# Shut_Down_Signal_Control.net
KiCad netlist of a schematic drawn in Altium Designer
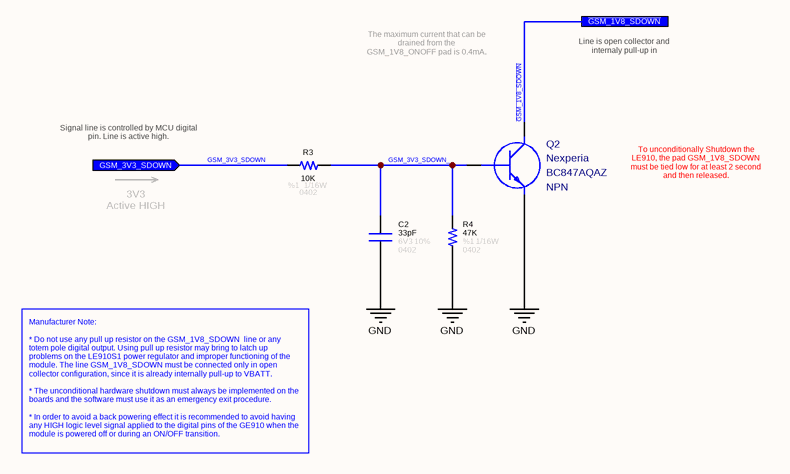
[diagram p0: Shut Down Signal Control.SchDoc]

(export (version "E")
  (design (tool "Eeschema 10.0.6"))
  (components
    (comp (ref "C2")
      (value "33pF")
      (footprint "CAPACITOR_0402")
      (description "Capacitor - 33pF [0402] (Ceramic)")
      (fields
        (field (name "MANUFACTURER PART NUMBER") "C0402C330J9RACAUTO")
        (field (name "TOLERANCE") "10%")
        (field (name "CASE") "0402")
        (field (name "VOLTAGE") "6V3")
      )
      (libsource (lib "P101DA_Library") (part "Capacitor - 33pF [0402-6V3]"))
    )
    (comp (ref "Q2")
      (value "BC847AQAZ")
      (footprint "SOT1215")
      (description "Bipolar NPN Transistors")
      (fields
        (field (name "MANUFACTURER NAME") "Nexperia")
        (field (name "MANUFACTURER PART NUMBER") "BC847AQAZ")
        (field (name "POLARITY") "NPN")
      )
      (libsource (lib "P101DA_Library") (part "Transistor - BC847"))
    )
    (comp (ref "R3")
      (value "10K")
      (footprint "RESISTOR_0402")
      (description "Thick Film Resistors - SMD 1/16 W 10 KOhm 1%")
      (fields
        (field (name "MANUFACTURER PART NUMBER") "CRCW040210K0FKED")
        (field (name "TOLERANCE") "%1")
        (field (name "CASE") "0402")
        (field (name "POWER") "1/16W")
        (field (name "Comment") "10K - 0402 - %1 - 1/16W")
      )
      (libsource (lib "P101DA_Library") (part "Resistor - 10K [0402]"))
    )
    (comp (ref "R4")
      (value "47K")
      (footprint "RESISTOR_0402")
      (description "Thick Film Resistors - SMD 1/16 W 47 KOhm 1%")
      (fields
        (field (name "MANUFACTURER PART NUMBER") "CRCW040247K0FKED")
        (field (name "TOLERANCE") "%1")
        (field (name "CASE") "0402")
        (field (name "POWER") "1/16W")
        (field (name "Comment") "47K - 0402 - %1 - 1/16W")
      )
      (libsource (lib "P101DA_Library") (part "Resistor - 47K [0402]"))
    )
  )
  (nets
    (net (code "1") (name "/GSM_3V3_SDOWN") (class "Default")
      (node (ref "R3") (pin "2") (pinfunction "2_2") (pintype "passive"))
    )
    (net (code "2") (name "/GSM_3V3_SDOWN_") (class "Default")
      (node (ref "C2") (pin "2") (pinfunction "2_2") (pintype "passive"))
      (node (ref "Q2") (pin "1") (pinfunction "B_1") (pintype "passive"))
      (node (ref "R3") (pin "1") (pinfunction "1_1") (pintype "passive"))
      (node (ref "R4") (pin "2") (pinfunction "2_2") (pintype "passive"))
    )
    (net (code "3") (name "/~{GSM_1V8_SDOWN}") (class "Default")
      (node (ref "Q2") (pin "3") (pinfunction "C_3") (pintype "passive"))
    )
    (net (code "4") (name "GND") (class "Default")
      (node (ref "C2") (pin "1") (pinfunction "1_1") (pintype "passive"))
      (node (ref "Q2") (pin "2") (pinfunction "E_2") (pintype "passive"))
      (node (ref "R4") (pin "1") (pinfunction "1_1") (pintype "passive"))
    )
  )
)
